# TinyIRCam-breakout-mk-2_0.net
KiCad netlist of a schematic drawn in EAGLE
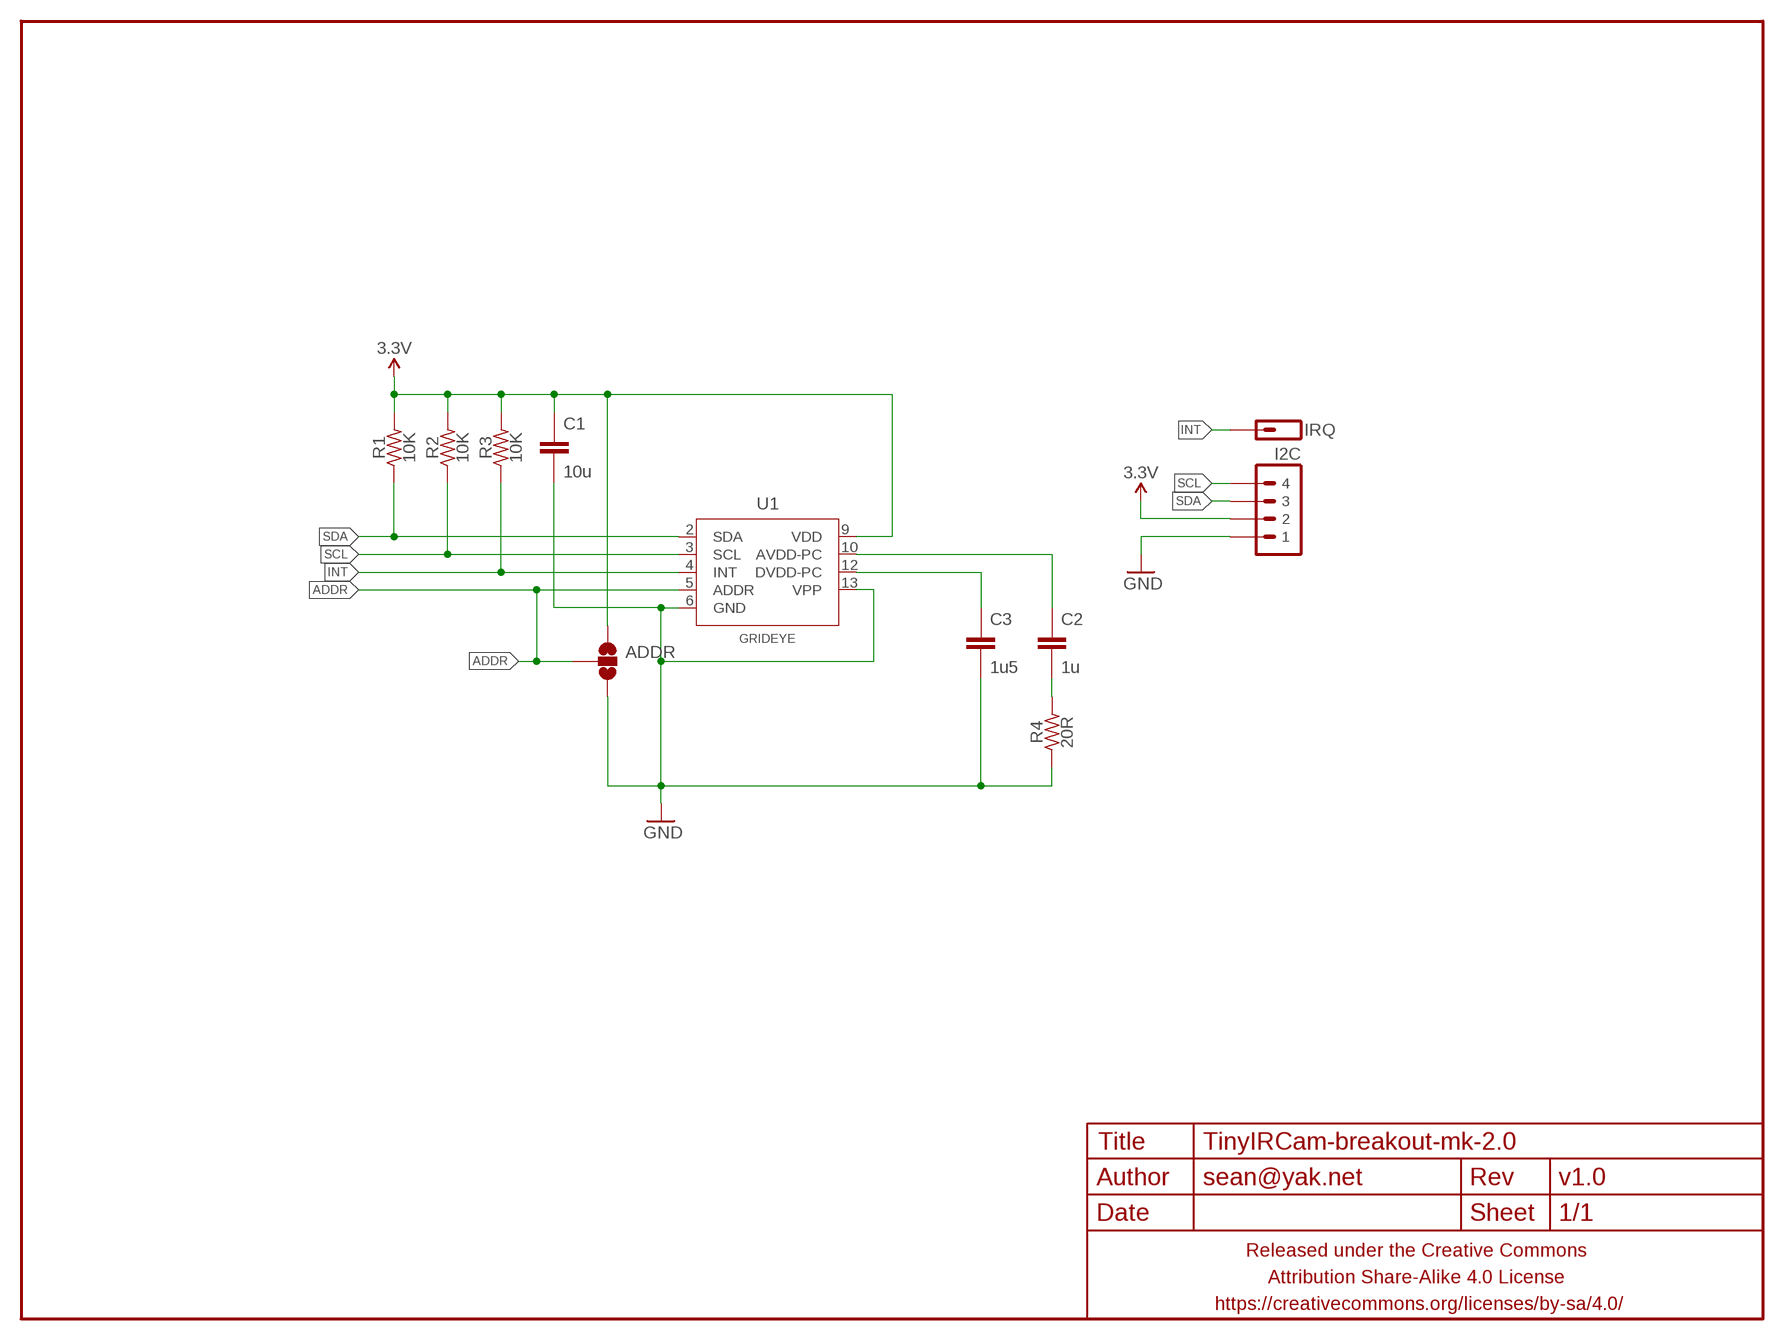
[diagram p0: schematic, sheet 1]

(export (version "E")
  (design (tool "Eeschema 10.0.6"))
  (components
    (comp (ref "ADDR")
      (value "JUMPER-PAD-3-NOSMALLER")
      (footprint "eagle-import:PAD-JUMPER-3-NO_YES_SILK_FULL_BOX_SMALLER")
      (libsource (lib "eagle-import") (part "JUMPER-PAD-3-NOSMALLER"))
    )
    (comp (ref "C1")
      (value "10u")
      (footprint "eagle-import:C0603-TIGHTER")
      (libsource (lib "eagle-import") (part "CAPACITOR-CERAMICC0603-TIGHTER"))
    )
    (comp (ref "C2")
      (value "1u")
      (footprint "eagle-import:C0603-TIGHTER")
      (libsource (lib "eagle-import") (part "CAPACITOR-CERAMICC0603-TIGHTER"))
    )
    (comp (ref "C3")
      (value "1u5")
      (footprint "eagle-import:C0603-TIGHTER")
      (libsource (lib "eagle-import") (part "CAPACITOR-CERAMICC0603-TIGHTER"))
    )
    (comp (ref "FRAME1")
      (value "FRAME-LETTERNO_PACKAGE")
      (footprint "eagle-import:DUMMY")
      (fields (field (name "DESIGNER") "sean@yak.net") (field (name "VERSION") "v1.0"))
      (libsource (lib "eagle-import") (part "FRAME-LETTERNO_PACKAGE"))
    )
    (comp (ref "I2C")
      (value "M04PTH-CENTERED")
      (footprint "eagle-import:1X04-PTH-VERT-CENTER")
      (libsource (lib "eagle-import") (part "M04PTH-CENTERED"))
    )
    (comp (ref "IRQ")
      (value "M01PTH")
      (footprint "eagle-import:1X01")
      (libsource (lib "eagle-import") (part "M01PTH"))
    )
    (comp (ref "R1")
      (value "10K")
      (footprint "eagle-import:R0603-TIGHTER")
      (libsource (lib "eagle-import") (part "RESISTORR0603-TIGHTER"))
    )
    (comp (ref "R2")
      (value "10K")
      (footprint "eagle-import:R0603-TIGHTER")
      (libsource (lib "eagle-import") (part "RESISTORR0603-TIGHTER"))
    )
    (comp (ref "R3")
      (value "10K")
      (footprint "eagle-import:R0603-TIGHTER")
      (libsource (lib "eagle-import") (part "RESISTORR0603-TIGHTER"))
    )
    (comp (ref "R4")
      (value "20R")
      (footprint "eagle-import:R0603-TIGHTER")
      (libsource (lib "eagle-import") (part "RESISTORR0603-TIGHTER"))
    )
    (comp (ref "U1")
      (value "GRIDEYE")
      (footprint "eagle-import:GRIDEYE-FATTER")
      (libsource (lib "eagle-import") (part "GRIDEYEFATTER"))
    )
  )
  (nets
    (net (code "1") (name "3.3V") (class "Default")
      (node (ref "ADDR") (pin "1") (pinfunction "1_1") (pintype "passive"))
      (node (ref "C1") (pin "1") (pinfunction "1_1") (pintype "passive"))
      (node (ref "I2C") (pin "2") (pinfunction "2_2") (pintype "passive"))
      (node (ref "R1") (pin "2") (pinfunction "2_2") (pintype "passive"))
      (node (ref "R2") (pin "2") (pinfunction "2_2") (pintype "passive"))
      (node (ref "R3") (pin "2") (pinfunction "2_2") (pintype "passive"))
      (node (ref "U1") (pin "9") (pinfunction "VDD_9") (pintype "bidirectional"))
    )
    (net (code "2") (name "ADDR") (class "Default")
      (node (ref "ADDR") (pin "2") (pinfunction "2_2") (pintype "passive"))
      (node (ref "U1") (pin "5") (pinfunction "ADDR_5") (pintype "bidirectional"))
    )
    (net (code "3") (name "GND") (class "Default")
      (node (ref "ADDR") (pin "3") (pinfunction "3_3") (pintype "passive"))
      (node (ref "C1") (pin "2") (pinfunction "2_2") (pintype "passive"))
      (node (ref "C3") (pin "2") (pinfunction "2_2") (pintype "passive"))
      (node (ref "I2C") (pin "1") (pinfunction "1_1") (pintype "passive"))
      (node (ref "R4") (pin "1") (pinfunction "1_1") (pintype "passive"))
      (node (ref "U1") (pin "13") (pinfunction "VPP_13") (pintype "bidirectional"))
      (node (ref "U1") (pin "6") (pinfunction "GND_6") (pintype "bidirectional"))
    )
    (net (code "4") (name "INT") (class "Default")
      (node (ref "IRQ") (pin "1") (pinfunction "1_1") (pintype "passive"))
      (node (ref "R3") (pin "1") (pinfunction "1_1") (pintype "passive"))
      (node (ref "U1") (pin "4") (pinfunction "INT_4") (pintype "bidirectional"))
    )
    (net (code "5") (name "Net-(C2-Pad2)") (class "Default")
      (node (ref "C2") (pin "2") (pinfunction "2_2") (pintype "passive"))
      (node (ref "R4") (pin "2") (pinfunction "2_2") (pintype "passive"))
    )
    (net (code "6") (name "Net-(U1-AVDD-PC)") (class "Default")
      (node (ref "C2") (pin "1") (pinfunction "1_1") (pintype "passive"))
      (node (ref "U1") (pin "10") (pinfunction "AVDD-PC_10") (pintype "bidirectional"))
    )
    (net (code "7") (name "Net-(U1-DVDD-PC)") (class "Default")
      (node (ref "C3") (pin "1") (pinfunction "1_1") (pintype "passive"))
      (node (ref "U1") (pin "12") (pinfunction "DVDD-PC_12") (pintype "bidirectional"))
    )
    (net (code "8") (name "SCL") (class "Default")
      (node (ref "I2C") (pin "4") (pinfunction "4_4") (pintype "passive"))
      (node (ref "R2") (pin "1") (pinfunction "1_1") (pintype "passive"))
      (node (ref "U1") (pin "3") (pinfunction "SCL_3") (pintype "bidirectional"))
    )
    (net (code "9") (name "SDA") (class "Default")
      (node (ref "I2C") (pin "3") (pinfunction "3_3") (pintype "passive"))
      (node (ref "R1") (pin "1") (pinfunction "1_1") (pintype "passive"))
      (node (ref "U1") (pin "2") (pinfunction "SDA_2") (pintype "bidirectional"))
    )
  )
)
